# screen.net
KiCad netlist of a schematic drawn in Altium Designer
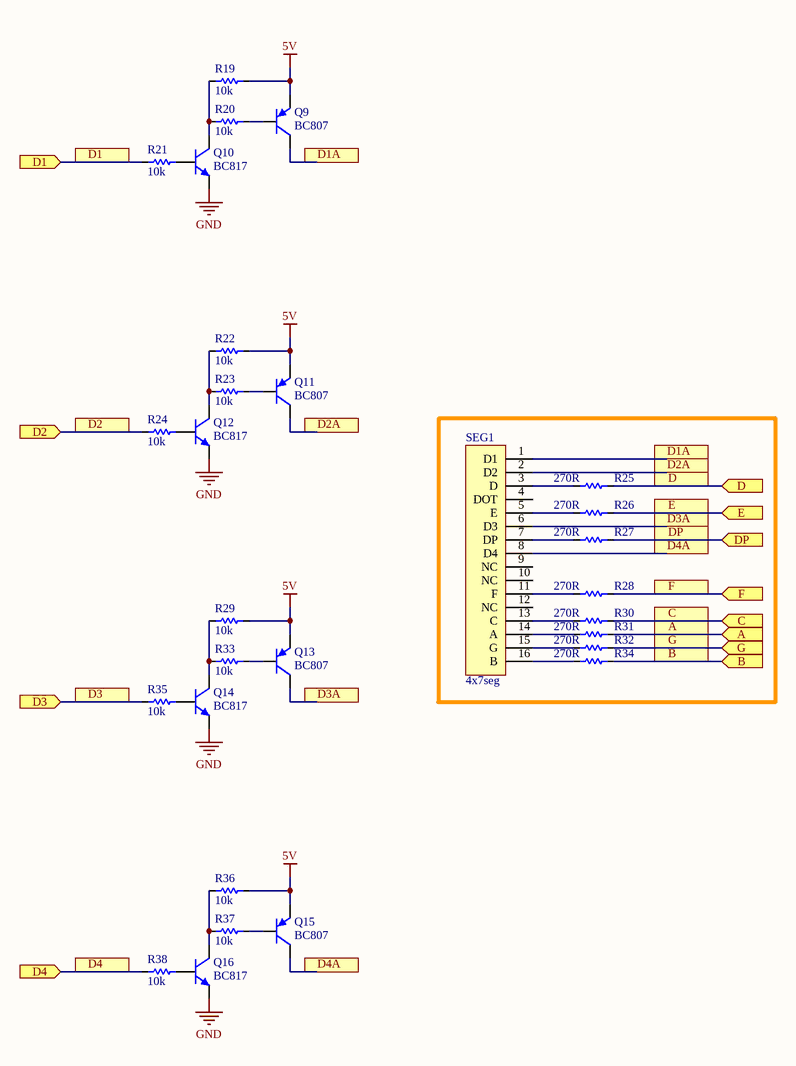
[diagram p0: screen.SchDoc]

(export (version "E")
  (design (tool "Eeschema 10.0.6"))
  (components
    (comp (ref "Q9") (value "BC807") (footprint "SOT23-3") (libsource (lib "A_Semi") (part "1-BJT-PNP")))
    (comp (ref "Q10")
      (value "BC817")
      (footprint "SOT23-3")
      (description "NPN General Purpose")
      (libsource (lib "A_Semi") (part "1-BJT_NPN"))
    )
    (comp (ref "Q11") (value "BC807") (footprint "SOT23-3") (libsource (lib "A_Semi") (part "1-BJT-PNP")))
    (comp (ref "Q12")
      (value "BC817")
      (footprint "SOT23-3")
      (description "NPN General Purpose")
      (libsource (lib "A_Semi") (part "1-BJT_NPN"))
    )
    (comp (ref "Q13") (value "BC807") (footprint "SOT23-3") (libsource (lib "A_Semi") (part "1-BJT-PNP")))
    (comp (ref "Q14")
      (value "BC817")
      (footprint "SOT23-3")
      (description "NPN General Purpose")
      (libsource (lib "A_Semi") (part "1-BJT_NPN"))
    )
    (comp (ref "Q15") (value "BC807") (footprint "SOT23-3") (libsource (lib "A_Semi") (part "1-BJT-PNP")))
    (comp (ref "Q16")
      (value "BC817")
      (footprint "SOT23-3")
      (description "NPN General Purpose")
      (libsource (lib "A_Semi") (part "1-BJT_NPN"))
    )
    (comp (ref "R19")
      (value "10k")
      (footprint "Size_0603_N")
      (description "=Value")
      (fields (field (name "TOLERANCE") ".1%") (field (name "Comment") "10k, *"))
      (libsource (lib "A_Passive") (part "-Res"))
    )
    (comp (ref "R20")
      (value "10k")
      (footprint "Size_0603_N")
      (description "=Value")
      (fields (field (name "TOLERANCE") ".1%") (field (name "Comment") "10k, *"))
      (libsource (lib "A_Passive") (part "-Res"))
    )
    (comp (ref "R21")
      (value "10k")
      (footprint "Size_0603_N")
      (description "=Value")
      (fields (field (name "TOLERANCE") ".1%") (field (name "Comment") "10k, *"))
      (libsource (lib "A_Passive") (part "-Res"))
    )
    (comp (ref "R22")
      (value "10k")
      (footprint "Size_0603_N")
      (description "=Value")
      (fields (field (name "TOLERANCE") ".1%") (field (name "Comment") "10k, *"))
      (libsource (lib "A_Passive") (part "-Res"))
    )
    (comp (ref "R23")
      (value "10k")
      (footprint "Size_0603_N")
      (description "=Value")
      (fields (field (name "TOLERANCE") ".1%") (field (name "Comment") "10k, *"))
      (libsource (lib "A_Passive") (part "-Res"))
    )
    (comp (ref "R24")
      (value "10k")
      (footprint "Size_0603_N")
      (description "=Value")
      (fields (field (name "TOLERANCE") ".1%") (field (name "Comment") "10k, *"))
      (libsource (lib "A_Passive") (part "-Res"))
    )
    (comp (ref "R25")
      (value "270R")
      (footprint "Size_0603_N")
      (description "=Value")
      (fields (field (name "TOLERANCE") "1%") (field (name "Comment") "270R, *"))
      (libsource (lib "A_Passive") (part "-Res"))
    )
    (comp (ref "R26")
      (value "270R")
      (footprint "Size_0603_N")
      (description "=Value")
      (fields (field (name "TOLERANCE") "1%") (field (name "Comment") "270R, *"))
      (libsource (lib "A_Passive") (part "-Res"))
    )
    (comp (ref "R27")
      (value "270R")
      (footprint "Size_0603_N")
      (description "=Value")
      (fields (field (name "TOLERANCE") "1%") (field (name "Comment") "270R, *"))
      (libsource (lib "A_Passive") (part "-Res"))
    )
    (comp (ref "R28")
      (value "270R")
      (footprint "Size_0603_N")
      (description "=Value")
      (fields (field (name "TOLERANCE") "1%") (field (name "Comment") "270R, *"))
      (libsource (lib "A_Passive") (part "-Res"))
    )
    (comp (ref "R29")
      (value "10k")
      (footprint "Size_0603_N")
      (description "=Value")
      (fields (field (name "TOLERANCE") ".1%") (field (name "Comment") "10k, *"))
      (libsource (lib "A_Passive") (part "-Res"))
    )
    (comp (ref "R30")
      (value "270R")
      (footprint "Size_0603_N")
      (description "=Value")
      (fields (field (name "TOLERANCE") "1%") (field (name "Comment") "270R, *"))
      (libsource (lib "A_Passive") (part "-Res"))
    )
    (comp (ref "R31")
      (value "270R")
      (footprint "Size_0603_N")
      (description "=Value")
      (fields (field (name "TOLERANCE") "1%") (field (name "Comment") "270R, *"))
      (libsource (lib "A_Passive") (part "-Res"))
    )
    (comp (ref "R32")
      (value "270R")
      (footprint "Size_0603_N")
      (description "=Value")
      (fields (field (name "TOLERANCE") "1%") (field (name "Comment") "270R, *"))
      (libsource (lib "A_Passive") (part "-Res"))
    )
    (comp (ref "R33")
      (value "10k")
      (footprint "Size_0603_N")
      (description "=Value")
      (fields (field (name "TOLERANCE") ".1%") (field (name "Comment") "10k, *"))
      (libsource (lib "A_Passive") (part "-Res"))
    )
    (comp (ref "R34")
      (value "270R")
      (footprint "Size_0603_N")
      (description "=Value")
      (fields (field (name "TOLERANCE") "1%") (field (name "Comment") "270R, *"))
      (libsource (lib "A_Passive") (part "-Res"))
    )
    (comp (ref "R35")
      (value "10k")
      (footprint "Size_0603_N")
      (description "=Value")
      (fields (field (name "TOLERANCE") ".1%") (field (name "Comment") "10k, *"))
      (libsource (lib "A_Passive") (part "-Res"))
    )
    (comp (ref "R36")
      (value "10k")
      (footprint "Size_0603_N")
      (description "=Value")
      (fields (field (name "TOLERANCE") ".1%") (field (name "Comment") "10k, *"))
      (libsource (lib "A_Passive") (part "-Res"))
    )
    (comp (ref "R37")
      (value "10k")
      (footprint "Size_0603_N")
      (description "=Value")
      (fields (field (name "TOLERANCE") ".1%") (field (name "Comment") "10k, *"))
      (libsource (lib "A_Passive") (part "-Res"))
    )
    (comp (ref "R38")
      (value "10k")
      (footprint "Size_0603_N")
      (description "=Value")
      (fields (field (name "TOLERANCE") ".1%") (field (name "Comment") "10k, *"))
      (libsource (lib "A_Passive") (part "-Res"))
    )
    (comp (ref "SEG1") (value "4x7seg") (footprint "LTC-4627JR") (libsource (lib "A_Semi") (part "4x7seg")))
  )
  (nets
    (net (code "1") (name "/A") (class "Default")
      (node (ref "R31") (pin "2") (pinfunction "2_2") (pintype "passive"))
    )
    (net (code "2") (name "/B") (class "Default")
      (node (ref "R34") (pin "2") (pinfunction "2_2") (pintype "passive"))
    )
    (net (code "3") (name "/C") (class "Default")
      (node (ref "R30") (pin "2") (pinfunction "2_2") (pintype "passive"))
    )
    (net (code "4") (name "/D") (class "Default")
      (node (ref "R25") (pin "2") (pinfunction "2_2") (pintype "passive"))
    )
    (net (code "5") (name "/D1") (class "Default")
      (node (ref "R21") (pin "2") (pinfunction "2_2") (pintype "passive"))
    )
    (net (code "6") (name "/D1A") (class "Default")
      (node (ref "Q9") (pin "3") (pinfunction "C_3") (pintype "passive"))
      (node (ref "SEG1") (pin "1") (pinfunction "D1_1") (pintype "passive"))
    )
    (net (code "7") (name "/D2") (class "Default")
      (node (ref "R24") (pin "2") (pinfunction "2_2") (pintype "passive"))
    )
    (net (code "8") (name "/D2A") (class "Default")
      (node (ref "Q11") (pin "3") (pinfunction "C_3") (pintype "passive"))
      (node (ref "SEG1") (pin "2") (pinfunction "D2_2") (pintype "passive"))
    )
    (net (code "9") (name "/D3") (class "Default")
      (node (ref "R35") (pin "2") (pinfunction "2_2") (pintype "passive"))
    )
    (net (code "10") (name "/D3A") (class "Default")
      (node (ref "Q13") (pin "3") (pinfunction "C_3") (pintype "passive"))
      (node (ref "SEG1") (pin "6") (pinfunction "D3_6") (pintype "passive"))
    )
    (net (code "11") (name "/D4") (class "Default")
      (node (ref "R38") (pin "2") (pinfunction "2_2") (pintype "passive"))
    )
    (net (code "12") (name "/D4A") (class "Default")
      (node (ref "Q15") (pin "3") (pinfunction "C_3") (pintype "passive"))
      (node (ref "SEG1") (pin "8") (pinfunction "D4_8") (pintype "passive"))
    )
    (net (code "13") (name "/DP") (class "Default")
      (node (ref "R27") (pin "2") (pinfunction "2_2") (pintype "passive"))
    )
    (net (code "14") (name "/E") (class "Default")
      (node (ref "R26") (pin "2") (pinfunction "2_2") (pintype "passive"))
    )
    (net (code "15") (name "/F") (class "Default")
      (node (ref "R28") (pin "2") (pinfunction "2_2") (pintype "passive"))
    )
    (net (code "16") (name "/G") (class "Default")
      (node (ref "R32") (pin "2") (pinfunction "2_2") (pintype "passive"))
    )
    (net (code "17") (name "5V") (class "Default")
      (node (ref "Q11") (pin "2") (pinfunction "E_2") (pintype "passive"))
      (node (ref "Q13") (pin "2") (pinfunction "E_2") (pintype "passive"))
      (node (ref "Q15") (pin "2") (pinfunction "E_2") (pintype "passive"))
      (node (ref "Q9") (pin "2") (pinfunction "E_2") (pintype "passive"))
      (node (ref "R19") (pin "1") (pinfunction "1_1") (pintype "passive"))
      (node (ref "R22") (pin "1") (pinfunction "1_1") (pintype "passive"))
      (node (ref "R29") (pin "1") (pinfunction "1_1") (pintype "passive"))
      (node (ref "R36") (pin "1") (pinfunction "1_1") (pintype "passive"))
    )
    (net (code "18") (name "GND") (class "Default")
      (node (ref "Q10") (pin "2") (pinfunction "E_2") (pintype "passive"))
      (node (ref "Q12") (pin "2") (pinfunction "E_2") (pintype "passive"))
      (node (ref "Q14") (pin "2") (pinfunction "E_2") (pintype "passive"))
      (node (ref "Q16") (pin "2") (pinfunction "E_2") (pintype "passive"))
    )
    (net (code "19") (name "Net-(Q9-B)") (class "Default")
      (node (ref "Q9") (pin "1") (pinfunction "B_1") (pintype "passive"))
      (node (ref "R20") (pin "1") (pinfunction "1_1") (pintype "passive"))
    )
    (net (code "20") (name "Net-(Q10-B)") (class "Default")
      (node (ref "Q10") (pin "1") (pinfunction "B_1") (pintype "passive"))
      (node (ref "R21") (pin "1") (pinfunction "1_1") (pintype "passive"))
    )
    (net (code "21") (name "Net-(Q10-C)") (class "Default")
      (node (ref "Q10") (pin "3") (pinfunction "C_3") (pintype "passive"))
      (node (ref "R19") (pin "2") (pinfunction "2_2") (pintype "passive"))
      (node (ref "R20") (pin "2") (pinfunction "2_2") (pintype "passive"))
    )
    (net (code "22") (name "Net-(Q11-B)") (class "Default")
      (node (ref "Q11") (pin "1") (pinfunction "B_1") (pintype "passive"))
      (node (ref "R23") (pin "1") (pinfunction "1_1") (pintype "passive"))
    )
    (net (code "23") (name "Net-(Q12-B)") (class "Default")
      (node (ref "Q12") (pin "1") (pinfunction "B_1") (pintype "passive"))
      (node (ref "R24") (pin "1") (pinfunction "1_1") (pintype "passive"))
    )
    (net (code "24") (name "Net-(Q12-C)") (class "Default")
      (node (ref "Q12") (pin "3") (pinfunction "C_3") (pintype "passive"))
      (node (ref "R22") (pin "2") (pinfunction "2_2") (pintype "passive"))
      (node (ref "R23") (pin "2") (pinfunction "2_2") (pintype "passive"))
    )
    (net (code "25") (name "Net-(Q13-B)") (class "Default")
      (node (ref "Q13") (pin "1") (pinfunction "B_1") (pintype "passive"))
      (node (ref "R33") (pin "1") (pinfunction "1_1") (pintype "passive"))
    )
    (net (code "26") (name "Net-(Q14-B)") (class "Default")
      (node (ref "Q14") (pin "1") (pinfunction "B_1") (pintype "passive"))
      (node (ref "R35") (pin "1") (pinfunction "1_1") (pintype "passive"))
    )
    (net (code "27") (name "Net-(Q14-C)") (class "Default")
      (node (ref "Q14") (pin "3") (pinfunction "C_3") (pintype "passive"))
      (node (ref "R29") (pin "2") (pinfunction "2_2") (pintype "passive"))
      (node (ref "R33") (pin "2") (pinfunction "2_2") (pintype "passive"))
    )
    (net (code "28") (name "Net-(Q15-B)") (class "Default")
      (node (ref "Q15") (pin "1") (pinfunction "B_1") (pintype "passive"))
      (node (ref "R37") (pin "1") (pinfunction "1_1") (pintype "passive"))
    )
    (net (code "29") (name "Net-(Q16-B)") (class "Default")
      (node (ref "Q16") (pin "1") (pinfunction "B_1") (pintype "passive"))
      (node (ref "R38") (pin "1") (pinfunction "1_1") (pintype "passive"))
    )
    (net (code "30") (name "Net-(Q16-C)") (class "Default")
      (node (ref "Q16") (pin "3") (pinfunction "C_3") (pintype "passive"))
      (node (ref "R36") (pin "2") (pinfunction "2_2") (pintype "passive"))
      (node (ref "R37") (pin "2") (pinfunction "2_2") (pintype "passive"))
    )
    (net (code "31") (name "Net-(SEG1-A)") (class "Default")
      (node (ref "R31") (pin "1") (pinfunction "1_1") (pintype "passive"))
      (node (ref "SEG1") (pin "14") (pinfunction "A_14") (pintype "passive"))
    )
    (net (code "32") (name "Net-(SEG1-B)") (class "Default")
      (node (ref "R34") (pin "1") (pinfunction "1_1") (pintype "passive"))
      (node (ref "SEG1") (pin "16") (pinfunction "B_16") (pintype "passive"))
    )
    (net (code "33") (name "Net-(SEG1-C)") (class "Default")
      (node (ref "R30") (pin "1") (pinfunction "1_1") (pintype "passive"))
      (node (ref "SEG1") (pin "13") (pinfunction "C_13") (pintype "passive"))
    )
    (net (code "34") (name "Net-(SEG1-D)") (class "Default")
      (node (ref "R25") (pin "1") (pinfunction "1_1") (pintype "passive"))
      (node (ref "SEG1") (pin "3") (pinfunction "D_3") (pintype "passive"))
    )
    (net (code "35") (name "Net-(SEG1-DP)") (class "Default")
      (node (ref "R27") (pin "1") (pinfunction "1_1") (pintype "passive"))
      (node (ref "SEG1") (pin "7") (pinfunction "DP_7") (pintype "passive"))
    )
    (net (code "36") (name "Net-(SEG1-E)") (class "Default")
      (node (ref "R26") (pin "1") (pinfunction "1_1") (pintype "passive"))
      (node (ref "SEG1") (pin "5") (pinfunction "E_5") (pintype "passive"))
    )
    (net (code "37") (name "Net-(SEG1-F)") (class "Default")
      (node (ref "R28") (pin "1") (pinfunction "1_1") (pintype "passive"))
      (node (ref "SEG1") (pin "11") (pinfunction "F_11") (pintype "passive"))
    )
    (net (code "38") (name "Net-(SEG1-G)") (class "Default")
      (node (ref "R32") (pin "1") (pinfunction "1_1") (pintype "passive"))
      (node (ref "SEG1") (pin "15") (pinfunction "G_15") (pintype "passive"))
    )
    (net (code "39") (name "unconnected-(SEG1-DOT-Pad4)") (class "Default")
      (node (ref "SEG1") (pin "4") (pinfunction "DOT_4") (pintype "passive"))
    )
    (net (code "40") (name "unconnected-(SEG1-NC-Pad9)") (class "Default")
      (node (ref "SEG1") (pin "9") (pinfunction "NC_9") (pintype "passive"))
    )
    (net (code "41") (name "unconnected-(SEG1-NC-Pad10)") (class "Default")
      (node (ref "SEG1") (pin "10") (pinfunction "NC_10") (pintype "passive"))
    )
    (net (code "42") (name "unconnected-(SEG1-NC-Pad12)") (class "Default")
      (node (ref "SEG1") (pin "12") (pinfunction "NC_12") (pintype "passive"))
    )
  )
)
